# HB-UNI-SenAct-8-8-RC_V1_1.net
KiCad netlist of a schematic drawn in EAGLE
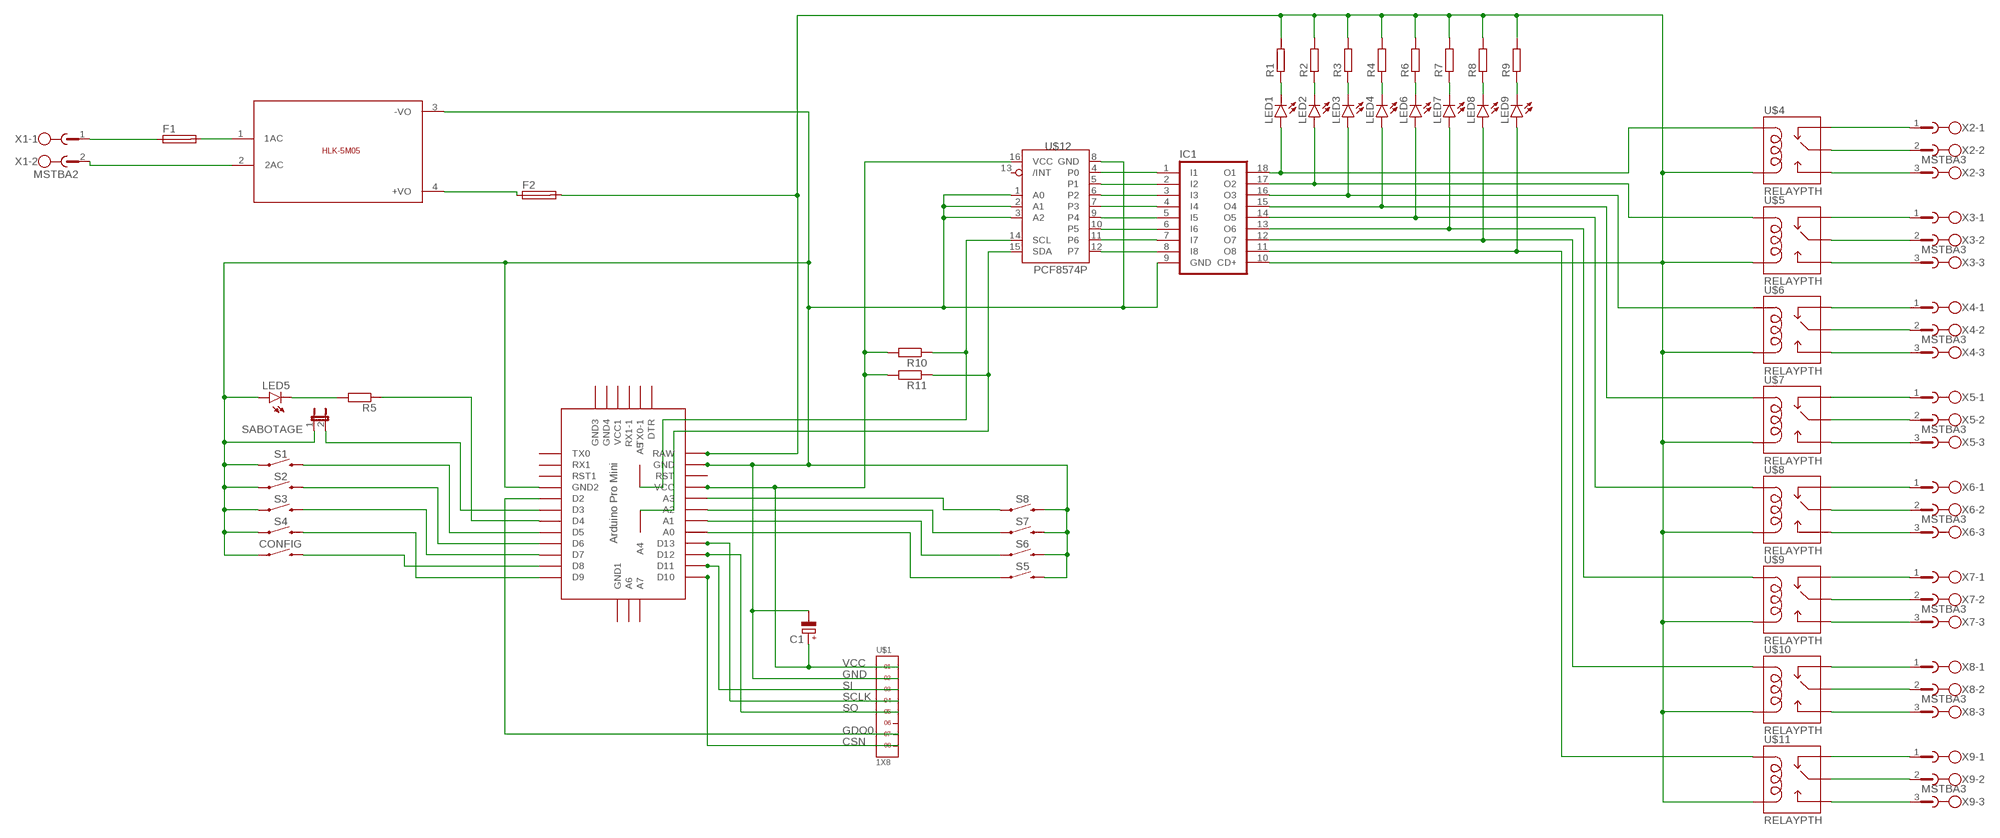
[diagram p0: schematic, sheet 1]

(export (version "E")
  (design (tool "Eeschema 10.0.6"))
  (components
    (comp (ref "C1")
      (value "CPOL-EUE2.5-5")
      (footprint "eagle-import:E2,5-5")
      (libsource (lib "eagle-import") (part "CPOL-EUE2.5-5"))
    )
    (comp (ref "CONFIG")
      (value "MOMENTARY-SWITCH-SPST-PTH-6.0MM-KIT")
      (footprint "eagle-import:TACTILE_SWITCH_PTH_6.0MM_KIT")
      (libsource (lib "eagle-import") (part "MOMENTARY-SWITCH-SPST-PTH-6.0MM-KIT"))
    )
    (comp (ref "F1")
      (value "SH22,5A")
      (footprint "eagle-import:SH22,5A")
      (fields (field (name "MPN") "0031.7701.11"))
      (libsource (lib "eagle-import") (part "SH22,5A"))
    )
    (comp (ref "F2")
      (value "SH22,5A")
      (footprint "eagle-import:SH22,5A")
      (fields (field (name "MPN") "0031.7701.11"))
      (libsource (lib "eagle-import") (part "SH22,5A"))
    )
    (comp (ref "IC1")
      (value "ULN2803A")
      (footprint "eagle-import:DIL18")
      (libsource (lib "eagle-import") (part "ULN2803A"))
    )
    (comp (ref "LED1")
      (value "LED3MM")
      (footprint "eagle-import:LED3MM")
      (libsource (lib "eagle-import") (part "LED3MM"))
    )
    (comp (ref "LED2")
      (value "LED3MM")
      (footprint "eagle-import:LED3MM")
      (libsource (lib "eagle-import") (part "LED3MM"))
    )
    (comp (ref "LED3")
      (value "LED3MM")
      (footprint "eagle-import:LED3MM")
      (libsource (lib "eagle-import") (part "LED3MM"))
    )
    (comp (ref "LED4")
      (value "LED3MM")
      (footprint "eagle-import:LED3MM")
      (libsource (lib "eagle-import") (part "LED3MM"))
    )
    (comp (ref "LED5")
      (value "LED3MM")
      (footprint "eagle-import:LED3MM")
      (libsource (lib "eagle-import") (part "LED3MM"))
    )
    (comp (ref "LED6")
      (value "LED3MM")
      (footprint "eagle-import:LED3MM")
      (libsource (lib "eagle-import") (part "LED3MM"))
    )
    (comp (ref "LED7")
      (value "LED3MM")
      (footprint "eagle-import:LED3MM")
      (libsource (lib "eagle-import") (part "LED3MM"))
    )
    (comp (ref "LED8")
      (value "LED3MM")
      (footprint "eagle-import:LED3MM")
      (libsource (lib "eagle-import") (part "LED3MM"))
    )
    (comp (ref "LED9")
      (value "LED3MM")
      (footprint "eagle-import:LED3MM")
      (libsource (lib "eagle-import") (part "LED3MM"))
    )
    (comp (ref "R1")
      (value "R-EU_0309/10")
      (footprint "eagle-import:0309_10")
      (libsource (lib "eagle-import") (part "R-EU_0309/10"))
    )
    (comp (ref "R2")
      (value "R-EU_0309/10")
      (footprint "eagle-import:0309_10")
      (libsource (lib "eagle-import") (part "R-EU_0309/10"))
    )
    (comp (ref "R3")
      (value "R-EU_0309/10")
      (footprint "eagle-import:0309_10")
      (libsource (lib "eagle-import") (part "R-EU_0309/10"))
    )
    (comp (ref "R4")
      (value "R-EU_0309/10")
      (footprint "eagle-import:0309_10")
      (libsource (lib "eagle-import") (part "R-EU_0309/10"))
    )
    (comp (ref "R5")
      (value "R-EU_0309/10")
      (footprint "eagle-import:0309_10")
      (libsource (lib "eagle-import") (part "R-EU_0309/10"))
    )
    (comp (ref "R6")
      (value "R-EU_0309/10")
      (footprint "eagle-import:0309_10")
      (libsource (lib "eagle-import") (part "R-EU_0309/10"))
    )
    (comp (ref "R7")
      (value "R-EU_0309/10")
      (footprint "eagle-import:0309_10")
      (libsource (lib "eagle-import") (part "R-EU_0309/10"))
    )
    (comp (ref "R8")
      (value "R-EU_0309/10")
      (footprint "eagle-import:0309_10")
      (libsource (lib "eagle-import") (part "R-EU_0309/10"))
    )
    (comp (ref "R9")
      (value "R-EU_0309/10")
      (footprint "eagle-import:0309_10")
      (libsource (lib "eagle-import") (part "R-EU_0309/10"))
    )
    (comp (ref "R10")
      (value "R-EU_0309/10")
      (footprint "eagle-import:0309_10")
      (libsource (lib "eagle-import") (part "R-EU_0309/10"))
    )
    (comp (ref "R11")
      (value "R-EU_0309/10")
      (footprint "eagle-import:0309_10")
      (libsource (lib "eagle-import") (part "R-EU_0309/10"))
    )
    (comp (ref "S1")
      (value "MOMENTARY-SWITCH-SPST-PTH-6.0MM")
      (footprint "eagle-import:TACTILE_SWITCH_PTH_6.0MM")
      (libsource (lib "eagle-import") (part "MOMENTARY-SWITCH-SPST-PTH-6.0MM"))
    )
    (comp (ref "S2")
      (value "MOMENTARY-SWITCH-SPST-PTH-6.0MM-KIT")
      (footprint "eagle-import:TACTILE_SWITCH_PTH_6.0MM_KIT")
      (libsource (lib "eagle-import") (part "MOMENTARY-SWITCH-SPST-PTH-6.0MM-KIT"))
    )
    (comp (ref "S3")
      (value "MOMENTARY-SWITCH-SPST-PTH-6.0MM-KIT")
      (footprint "eagle-import:TACTILE_SWITCH_PTH_6.0MM_KIT")
      (libsource (lib "eagle-import") (part "MOMENTARY-SWITCH-SPST-PTH-6.0MM-KIT"))
    )
    (comp (ref "S4")
      (value "MOMENTARY-SWITCH-SPST-PTH-6.0MM-KIT")
      (footprint "eagle-import:TACTILE_SWITCH_PTH_6.0MM_KIT")
      (libsource (lib "eagle-import") (part "MOMENTARY-SWITCH-SPST-PTH-6.0MM-KIT"))
    )
    (comp (ref "S5")
      (value "MOMENTARY-SWITCH-SPST-PTH-6.0MM-KIT")
      (footprint "eagle-import:TACTILE_SWITCH_PTH_6.0MM_KIT")
      (libsource (lib "eagle-import") (part "MOMENTARY-SWITCH-SPST-PTH-6.0MM-KIT"))
    )
    (comp (ref "S6")
      (value "MOMENTARY-SWITCH-SPST-PTH-6.0MM-KIT")
      (footprint "eagle-import:TACTILE_SWITCH_PTH_6.0MM_KIT")
      (libsource (lib "eagle-import") (part "MOMENTARY-SWITCH-SPST-PTH-6.0MM-KIT"))
    )
    (comp (ref "S7")
      (value "MOMENTARY-SWITCH-SPST-PTH-6.0MM-KIT")
      (footprint "eagle-import:TACTILE_SWITCH_PTH_6.0MM_KIT")
      (libsource (lib "eagle-import") (part "MOMENTARY-SWITCH-SPST-PTH-6.0MM-KIT"))
    )
    (comp (ref "S8")
      (value "MOMENTARY-SWITCH-SPST-PTH-6.0MM-KIT")
      (footprint "eagle-import:TACTILE_SWITCH_PTH_6.0MM_KIT")
      (libsource (lib "eagle-import") (part "MOMENTARY-SWITCH-SPST-PTH-6.0MM-KIT"))
    )
    (comp (ref "SABOTAGE")
      (value "JP1E")
      (footprint "eagle-import:JP1")
      (libsource (lib "eagle-import") (part "JP1E"))
    )
    (comp (ref "U$1")
      (value "1X8")
      (footprint "eagle-import:1X8")
      (libsource (lib "eagle-import") (part "1X8"))
    )
    (comp (ref "U$2")
      (value "ABK-PRO-MINI")
      (footprint "eagle-import:ABK-PRO-MINI")
      (libsource (lib "eagle-import") (part "ABK-PRO-MINI"))
    )
    (comp (ref "U$3")
      (value "5VDC/5W")
      (footprint "eagle-import:HLK-5M05")
      (libsource (lib "eagle-import") (part "HLK-5M05"))
    )
    (comp (ref "U$4")
      (value "RELAYPTH")
      (footprint "eagle-import:SRD-05VDC-SL-C")
      (libsource (lib "eagle-import") (part "RELAYPTH"))
    )
    (comp (ref "U$5")
      (value "RELAYPTH")
      (footprint "eagle-import:SRD-05VDC-SL-C")
      (libsource (lib "eagle-import") (part "RELAYPTH"))
    )
    (comp (ref "U$6")
      (value "RELAYPTH")
      (footprint "eagle-import:SRD-05VDC-SL-C")
      (libsource (lib "eagle-import") (part "RELAYPTH"))
    )
    (comp (ref "U$7")
      (value "RELAYPTH")
      (footprint "eagle-import:SRD-05VDC-SL-C")
      (libsource (lib "eagle-import") (part "RELAYPTH"))
    )
    (comp (ref "U$8")
      (value "RELAYPTH")
      (footprint "eagle-import:SRD-05VDC-SL-C")
      (libsource (lib "eagle-import") (part "RELAYPTH"))
    )
    (comp (ref "U$9")
      (value "RELAYPTH")
      (footprint "eagle-import:SRD-05VDC-SL-C")
      (libsource (lib "eagle-import") (part "RELAYPTH"))
    )
    (comp (ref "U$10")
      (value "RELAYPTH")
      (footprint "eagle-import:SRD-05VDC-SL-C")
      (libsource (lib "eagle-import") (part "RELAYPTH"))
    )
    (comp (ref "U$11")
      (value "RELAYPTH")
      (footprint "eagle-import:SRD-05VDC-SL-C")
      (libsource (lib "eagle-import") (part "RELAYPTH"))
    )
    (comp (ref "U$12")
      (value "PCF8574P")
      (footprint "eagle-import:DIL16")
      (libsource (lib "eagle-import") (part "PCF8574P"))
    )
    (comp (ref "X1")
      (value "MSTBA2")
      (footprint "eagle-import:MSTBA2")
      (fields (field (name "MF") "FARNELL") (field (name "MPN") "1757242"))
      (libsource (lib "eagle-import") (part "MSTBA2"))
    )
    (comp (ref "X2")
      (value "MSTBA3")
      (footprint "eagle-import:MSTBA3")
      (fields (field (name "MF") "FARNELL") (field (name "MPN") "1757255"))
      (libsource (lib "eagle-import") (part "MSTBA3"))
    )
    (comp (ref "X3")
      (value "MSTBA3")
      (footprint "eagle-import:MSTBA3")
      (fields (field (name "MF") "FARNELL") (field (name "MPN") "1757255"))
      (libsource (lib "eagle-import") (part "MSTBA3"))
    )
    (comp (ref "X4")
      (value "MSTBA3")
      (footprint "eagle-import:MSTBA3")
      (fields (field (name "MF") "FARNELL") (field (name "MPN") "1757255"))
      (libsource (lib "eagle-import") (part "MSTBA3"))
    )
    (comp (ref "X5")
      (value "MSTBA3")
      (footprint "eagle-import:MSTBA3")
      (fields (field (name "MF") "FARNELL") (field (name "MPN") "1757255"))
      (libsource (lib "eagle-import") (part "MSTBA3"))
    )
    (comp (ref "X6")
      (value "MSTBA3")
      (footprint "eagle-import:MSTBA3")
      (fields (field (name "MF") "FARNELL") (field (name "MPN") "1757255"))
      (libsource (lib "eagle-import") (part "MSTBA3"))
    )
    (comp (ref "X7")
      (value "MSTBA3")
      (footprint "eagle-import:MSTBA3")
      (fields (field (name "MF") "FARNELL") (field (name "MPN") "1757255"))
      (libsource (lib "eagle-import") (part "MSTBA3"))
    )
    (comp (ref "X8")
      (value "MSTBA3")
      (footprint "eagle-import:MSTBA3")
      (fields (field (name "MF") "FARNELL") (field (name "MPN") "1757255"))
      (libsource (lib "eagle-import") (part "MSTBA3"))
    )
    (comp (ref "X9")
      (value "MSTBA3")
      (footprint "eagle-import:MSTBA3")
      (fields (field (name "MF") "FARNELL") (field (name "MPN") "1757255"))
      (libsource (lib "eagle-import") (part "MSTBA3"))
    )
  )
  (nets
    (net (code "1") (name "/CSN") (class "Default")
      (node (ref "U$1") (pin "8") (pinfunction "8_8") (pintype "bidirectional"))
      (node (ref "U$2") (pin "D10") (pinfunction "D10_D10") (pintype "bidirectional"))
    )
    (net (code "2") (name "/GDO0") (class "Default")
      (node (ref "U$1") (pin "7") (pinfunction "7_7") (pintype "bidirectional"))
      (node (ref "U$2") (pin "D2") (pinfunction "D2_D2") (pintype "bidirectional"))
    )
    (net (code "3") (name "/GND") (class "Default")
      (node (ref "C1") (pin "-") (pinfunction "-_-") (pintype "passive"))
      (node (ref "CONFIG") (pin "1") (pinfunction "1_1") (pintype "passive"))
      (node (ref "IC1") (pin "9") (pinfunction "GND_9") (pintype "power_in"))
      (node (ref "LED5") (pin "A") (pinfunction "A_A") (pintype "passive"))
      (node (ref "S1") (pin "1") (pinfunction "1_1") (pintype "passive"))
      (node (ref "S2") (pin "1") (pinfunction "1_1") (pintype "passive"))
      (node (ref "S3") (pin "1") (pinfunction "1_1") (pintype "passive"))
      (node (ref "S4") (pin "1") (pinfunction "1_1") (pintype "passive"))
      (node (ref "S5") (pin "3") (pinfunction "2_3") (pintype "passive"))
      (node (ref "S6") (pin "3") (pinfunction "2_3") (pintype "passive"))
      (node (ref "S7") (pin "3") (pinfunction "2_3") (pintype "passive"))
      (node (ref "S8") (pin "3") (pinfunction "2_3") (pintype "passive"))
      (node (ref "SABOTAGE") (pin "1") (pinfunction "1_1") (pintype "passive"))
      (node (ref "U$1") (pin "2") (pinfunction "2_2") (pintype "bidirectional"))
      (node (ref "U$12") (pin "1") (pinfunction "A0_1") (pintype "input"))
      (node (ref "U$12") (pin "2") (pinfunction "A1_2") (pintype "input"))
      (node (ref "U$12") (pin "3") (pinfunction "A2_3") (pintype "input"))
      (node (ref "U$12") (pin "8") (pinfunction "GND_8") (pintype "power_in"))
      (node (ref "U$2") (pin "GND") (pinfunction "GND_GND") (pintype "bidirectional"))
      (node (ref "U$2") (pin "GND1") (pinfunction "GND2_GND1") (pintype "bidirectional"))
      (node (ref "U$3") (pin "3") (pinfunction "-VO_3") (pintype "bidirectional"))
    )
    (net (code "4") (name "/SCLK") (class "Default")
      (node (ref "U$1") (pin "4") (pinfunction "4_4") (pintype "bidirectional"))
      (node (ref "U$2") (pin "D13") (pinfunction "D13_D13") (pintype "bidirectional"))
    )
    (net (code "5") (name "/SI") (class "Default")
      (node (ref "U$1") (pin "3") (pinfunction "3_3") (pintype "bidirectional"))
      (node (ref "U$2") (pin "D11") (pinfunction "D11_D11") (pintype "bidirectional"))
    )
    (net (code "6") (name "/SO") (class "Default")
      (node (ref "U$1") (pin "5") (pinfunction "5_5") (pintype "bidirectional"))
      (node (ref "U$2") (pin "D12") (pinfunction "D12_D12") (pintype "bidirectional"))
    )
    (net (code "7") (name "/VCC") (class "Default")
      (node (ref "C1") (pin "+") (pinfunction "+_+") (pintype "passive"))
      (node (ref "R10") (pin "2") (pinfunction "2_2") (pintype "passive"))
      (node (ref "R11") (pin "2") (pinfunction "2_2") (pintype "passive"))
      (node (ref "U$1") (pin "1") (pinfunction "1_1") (pintype "bidirectional"))
      (node (ref "U$12") (pin "16") (pinfunction "VCC_16") (pintype "power_in"))
      (node (ref "U$2") (pin "VCC") (pinfunction "VCC_VCC") (pintype "bidirectional"))
    )
    (net (code "8") (name "Net-(CONFIG-2)") (class "Default")
      (node (ref "CONFIG") (pin "3") (pinfunction "2_3") (pintype "passive"))
      (node (ref "U$2") (pin "D8") (pinfunction "D8_D8") (pintype "bidirectional"))
    )
    (net (code "9") (name "Net-(F1-Pad1)") (class "Default")
      (node (ref "F1") (pin "1") (pinfunction "1_1") (pintype "passive"))
      (node (ref "X1") (pin "1") (pinfunction "1_1") (pintype "passive"))
    )
    (net (code "10") (name "Net-(IC1-CD+)") (class "Default")
      (node (ref "F2") (pin "2") (pinfunction "2_2") (pintype "passive"))
      (node (ref "IC1") (pin "10") (pinfunction "CD+_10") (pintype "passive"))
      (node (ref "R1") (pin "2") (pinfunction "2_2") (pintype "passive"))
      (node (ref "R2") (pin "2") (pinfunction "2_2") (pintype "passive"))
      (node (ref "R3") (pin "2") (pinfunction "2_2") (pintype "passive"))
      (node (ref "R4") (pin "2") (pinfunction "2_2") (pintype "passive"))
      (node (ref "R6") (pin "2") (pinfunction "2_2") (pintype "passive"))
      (node (ref "R7") (pin "2") (pinfunction "2_2") (pintype "passive"))
      (node (ref "R8") (pin "2") (pinfunction "2_2") (pintype "passive"))
      (node (ref "R9") (pin "2") (pinfunction "2_2") (pintype "passive"))
      (node (ref "U$10") (pin "COIL0") (pinfunction "COIL0_COIL0") (pintype "bidirectional"))
      (node (ref "U$11") (pin "COIL0") (pinfunction "COIL0_COIL0") (pintype "bidirectional"))
      (node (ref "U$2") (pin "RAW") (pinfunction "RAW_RAW") (pintype "bidirectional"))
      (node (ref "U$4") (pin "COIL0") (pinfunction "COIL0_COIL0") (pintype "bidirectional"))
      (node (ref "U$5") (pin "COIL0") (pinfunction "COIL0_COIL0") (pintype "bidirectional"))
      (node (ref "U$6") (pin "COIL0") (pinfunction "COIL0_COIL0") (pintype "bidirectional"))
      (node (ref "U$7") (pin "COIL0") (pinfunction "COIL0_COIL0") (pintype "bidirectional"))
      (node (ref "U$8") (pin "COIL0") (pinfunction "COIL0_COIL0") (pintype "bidirectional"))
      (node (ref "U$9") (pin "COIL0") (pinfunction "COIL0_COIL0") (pintype "bidirectional"))
    )
    (net (code "11") (name "Net-(IC1-I1)") (class "Default")
      (node (ref "IC1") (pin "1") (pinfunction "I1_1") (pintype "input"))
      (node (ref "U$12") (pin "4") (pinfunction "P0_4") (pintype "bidirectional"))
    )
    (net (code "12") (name "Net-(IC1-I2)") (class "Default")
      (node (ref "IC1") (pin "2") (pinfunction "I2_2") (pintype "input"))
      (node (ref "U$12") (pin "5") (pinfunction "P1_5") (pintype "bidirectional"))
    )
    (net (code "13") (name "Net-(IC1-I3)") (class "Default")
      (node (ref "IC1") (pin "3") (pinfunction "I3_3") (pintype "input"))
      (node (ref "U$12") (pin "6") (pinfunction "P2_6") (pintype "bidirectional"))
    )
    (net (code "14") (name "Net-(IC1-I4)") (class "Default")
      (node (ref "IC1") (pin "4") (pinfunction "I4_4") (pintype "input"))
      (node (ref "U$12") (pin "7") (pinfunction "P3_7") (pintype "bidirectional"))
    )
    (net (code "15") (name "Net-(IC1-I5)") (class "Default")
      (node (ref "IC1") (pin "5") (pinfunction "I5_5") (pintype "input"))
      (node (ref "U$12") (pin "9") (pinfunction "P4_9") (pintype "bidirectional"))
    )
    (net (code "16") (name "Net-(IC1-I6)") (class "Default")
      (node (ref "IC1") (pin "6") (pinfunction "I6_6") (pintype "input"))
      (node (ref "U$12") (pin "10") (pinfunction "P5_10") (pintype "bidirectional"))
    )
    (net (code "17") (name "Net-(IC1-I7)") (class "Default")
      (node (ref "IC1") (pin "7") (pinfunction "I7_7") (pintype "input"))
      (node (ref "U$12") (pin "11") (pinfunction "P6_11") (pintype "bidirectional"))
    )
    (net (code "18") (name "Net-(IC1-I8)") (class "Default")
      (node (ref "IC1") (pin "8") (pinfunction "I8_8") (pintype "input"))
      (node (ref "U$12") (pin "12") (pinfunction "P7_12") (pintype "bidirectional"))
    )
    (net (code "19") (name "Net-(IC1-O1)") (class "Default")
      (node (ref "IC1") (pin "18") (pinfunction "O1_18") (pintype "open_collector"))
      (node (ref "LED1") (pin "A") (pinfunction "A_A") (pintype "passive"))
      (node (ref "U$4") (pin "COIL1") (pinfunction "COIL1_COIL1") (pintype "bidirectional"))
    )
    (net (code "20") (name "Net-(IC1-O2)") (class "Default")
      (node (ref "IC1") (pin "17") (pinfunction "O2_17") (pintype "open_collector"))
      (node (ref "LED2") (pin "A") (pinfunction "A_A") (pintype "passive"))
      (node (ref "U$5") (pin "COIL1") (pinfunction "COIL1_COIL1") (pintype "bidirectional"))
    )
    (net (code "21") (name "Net-(IC1-O3)") (class "Default")
      (node (ref "IC1") (pin "16") (pinfunction "O3_16") (pintype "open_collector"))
      (node (ref "LED3") (pin "A") (pinfunction "A_A") (pintype "passive"))
      (node (ref "U$6") (pin "COIL1") (pinfunction "COIL1_COIL1") (pintype "bidirectional"))
    )
    (net (code "22") (name "Net-(IC1-O4)") (class "Default")
      (node (ref "IC1") (pin "15") (pinfunction "O4_15") (pintype "open_collector"))
      (node (ref "LED4") (pin "A") (pinfunction "A_A") (pintype "passive"))
      (node (ref "U$7") (pin "COIL1") (pinfunction "COIL1_COIL1") (pintype "bidirectional"))
    )
    (net (code "23") (name "Net-(IC1-O5)") (class "Default")
      (node (ref "IC1") (pin "14") (pinfunction "O5_14") (pintype "open_collector"))
      (node (ref "LED6") (pin "A") (pinfunction "A_A") (pintype "passive"))
      (node (ref "U$8") (pin "COIL1") (pinfunction "COIL1_COIL1") (pintype "bidirectional"))
    )
    (net (code "24") (name "Net-(IC1-O6)") (class "Default")
      (node (ref "IC1") (pin "13") (pinfunction "O6_13") (pintype "open_collector"))
      (node (ref "LED7") (pin "A") (pinfunction "A_A") (pintype "passive"))
      (node (ref "U$9") (pin "COIL1") (pinfunction "COIL1_COIL1") (pintype "bidirectional"))
    )
    (net (code "25") (name "Net-(IC1-O7)") (class "Default")
      (node (ref "IC1") (pin "12") (pinfunction "O7_12") (pintype "open_collector"))
      (node (ref "LED8") (pin "A") (pinfunction "A_A") (pintype "passive"))
      (node (ref "U$10") (pin "COIL1") (pinfunction "COIL1_COIL1") (pintype "bidirectional"))
    )
    (net (code "26") (name "Net-(IC1-O8)") (class "Default")
      (node (ref "IC1") (pin "11") (pinfunction "O8_11") (pintype "open_collector"))
      (node (ref "LED9") (pin "A") (pinfunction "A_A") (pintype "passive"))
      (node (ref "U$11") (pin "COIL1") (pinfunction "COIL1_COIL1") (pintype "bidirectional"))
    )
    (net (code "27") (name "Net-(LED1-C)") (class "Default")
      (node (ref "LED1") (pin "K") (pinfunction "C_K") (pintype "passive"))
      (node (ref "R1") (pin "1") (pinfunction "1_1") (pintype "passive"))
    )
    (net (code "28") (name "Net-(LED2-C)") (class "Default")
      (node (ref "LED2") (pin "K") (pinfunction "C_K") (pintype "passive"))
      (node (ref "R2") (pin "1") (pinfunction "1_1") (pintype "passive"))
    )
    (net (code "29") (name "Net-(LED3-C)") (class "Default")
      (node (ref "LED3") (pin "K") (pinfunction "C_K") (pintype "passive"))
      (node (ref "R3") (pin "1") (pinfunction "1_1") (pintype "passive"))
    )
    (net (code "30") (name "Net-(LED4-C)") (class "Default")
      (node (ref "LED4") (pin "K") (pinfunction "C_K") (pintype "passive"))
      (node (ref "R4") (pin "1") (pinfunction "1_1") (pintype "passive"))
    )
    (net (code "31") (name "Net-(LED5-C)") (class "Default")
      (node (ref "LED5") (pin "K") (pinfunction "C_K") (pintype "passive"))
      (node (ref "R5") (pin "2") (pinfunction "2_2") (pintype "passive"))
    )
    (net (code "32") (name "Net-(LED6-C)") (class "Default")
      (node (ref "LED6") (pin "K") (pinfunction "C_K") (pintype "passive"))
      (node (ref "R6") (pin "1") (pinfunction "1_1") (pintype "passive"))
    )
    (net (code "33") (name "Net-(LED7-C)") (class "Default")
      (node (ref "LED7") (pin "K") (pinfunction "C_K") (pintype "passive"))
      (node (ref "R7") (pin "1") (pinfunction "1_1") (pintype "passive"))
    )
    (net (code "34") (name "Net-(LED8-C)") (class "Default")
      (node (ref "LED8") (pin "K") (pinfunction "C_K") (pintype "passive"))
      (node (ref "R8") (pin "1") (pinfunction "1_1") (pintype "passive"))
    )
    (net (code "35") (name "Net-(LED9-C)") (class "Default")
      (node (ref "LED9") (pin "K") (pinfunction "C_K") (pintype "passive"))
      (node (ref "R9") (pin "1") (pinfunction "1_1") (pintype "passive"))
    )
    (net (code "36") (name "Net-(R5-Pad1)") (class "Default")
      (node (ref "R5") (pin "1") (pinfunction "1_1") (pintype "passive"))
      (node (ref "U$2") (pin "D4") (pinfunction "D4_D4") (pintype "bidirectional"))
    )
    (net (code "37") (name "Net-(S1-2)") (class "Default")
      (node (ref "S1") (pin "3") (pinfunction "2_3") (pintype "passive"))
      (node (ref "U$2") (pin "D5") (pinfunction "D5_D5") (pintype "bidirectional"))
    )
    (net (code "38") (name "Net-(S2-2)") (class "Default")
      (node (ref "S2") (pin "3") (pinfunction "2_3") (pintype "passive"))
      (node (ref "U$2") (pin "D6") (pinfunction "D6_D6") (pintype "bidirectional"))
    )
    (net (code "39") (name "Net-(S3-2)") (class "Default")
      (node (ref "S3") (pin "3") (pinfunction "2_3") (pintype "passive"))
      (node (ref "U$2") (pin "D7") (pinfunction "D7_D7") (pintype "bidirectional"))
    )
    (net (code "40") (name "Net-(S4-2)") (class "Default")
      (node (ref "S4") (pin "3") (pinfunction "2_3") (pintype "passive"))
      (node (ref "U$2") (pin "D9") (pinfunction "D9_D9") (pintype "bidirectional"))
    )
    (net (code "41") (name "Net-(S5-Pad1)") (class "Default")
      (node (ref "S5") (pin "1") (pinfunction "1_1") (pintype "passive"))
      (node (ref "U$2") (pin "A0") (pinfunction "A0_A0") (pintype "bidirectional"))
    )
    (net (code "42") (name "Net-(S6-Pad1)") (class "Default")
      (node (ref "S6") (pin "1") (pinfunction "1_1") (pintype "passive"))
      (node (ref "U$2") (pin "A1") (pinfunction "A1_A1") (pintype "bidirectional"))
    )
    (net (code "43") (name "Net-(S7-Pad1)") (class "Default")
      (node (ref "S7") (pin "1") (pinfunction "1_1") (pintype "passive"))
      (node (ref "U$2") (pin "A2") (pinfunction "A2_A2") (pintype "bidirectional"))
    )
    (net (code "44") (name "Net-(S8-Pad1)") (class "Default")
      (node (ref "S8") (pin "1") (pinfunction "1_1") (pintype "passive"))
      (node (ref "U$2") (pin "A3") (pinfunction "A3_A3") (pintype "bidirectional"))
    )
    (net (code "45") (name "Net-(SABOTAGE-Pad2)") (class "Default")
      (node (ref "SABOTAGE") (pin "2") (pinfunction "2_2") (pintype "passive"))
      (node (ref "U$2") (pin "D3") (pinfunction "D3_D3") (pintype "bidirectional"))
    )
    (net (code "46") (name "Net-(U$3-+VO)") (class "Default")
      (node (ref "F2") (pin "1") (pinfunction "1_1") (pintype "passive"))
      (node (ref "U$3") (pin "4") (pinfunction "+VO_4") (pintype "bidirectional"))
    )
    (net (code "47") (name "Net-(U$3-1AC)") (class "Default")
      (node (ref "F1") (pin "2") (pinfunction "2_2") (pintype "passive"))
      (node (ref "U$3") (pin "1") (pinfunction "1AC_1") (pintype "bidirectional"))
    )
    (net (code "48") (name "Net-(U$3-2AC)") (class "Default")
      (node (ref "U$3") (pin "2") (pinfunction "2AC_2") (pintype "bidirectional"))
      (node (ref "X1") (pin "2") (pinfunction "1_2") (pintype "passive"))
    )
    (net (code "49") (name "Net-(U$4-SWCLOSE)") (class "Default")
      (node (ref "U$4") (pin "SWCLOSED") (pinfunction "SWCLOSE_SWCLOSED") (pintype "bidirectional"))
      (node (ref "X2") (pin "1") (pinfunction "1_1") (pintype "passive"))
    )
    (net (code "50") (name "Net-(U$5-SWCLOSE)") (class "Default")
      (node (ref "U$5") (pin "SWCLOSED") (pinfunction "SWCLOSE_SWCLOSED") (pintype "bidirectional"))
      (node (ref "X3") (pin "1") (pinfunction "1_1") (pintype "passive"))
    )
    (net (code "51") (name "Net-(U$6-SWCLOSE)") (class "Default")
      (node (ref "U$6") (pin "SWCLOSED") (pinfunction "SWCLOSE_SWCLOSED") (pintype "bidirectional"))
      (node (ref "X4") (pin "1") (pinfunction "1_1") (pintype "passive"))
    )
    (net (code "52") (name "Net-(U$7-SWCLOSE)") (class "Default")
      (node (ref "U$7") (pin "SWCLOSED") (pinfunction "SWCLOSE_SWCLOSED") (pintype "bidirectional"))
      (node (ref "X5") (pin "1") (pinfunction "1_1") (pintype "passive"))
    )
    (net (code "53") (name "Net-(U$8-SWCLOSE)") (class "Default")
      (node (ref "U$8") (pin "SWCLOSED") (pinfunction "SWCLOSE_SWCLOSED") (pintype "bidirectional"))
      (node (ref "X6") (pin "1") (pinfunction "1_1") (pintype "passive"))
    )
    (net (code "54") (name "Net-(U$9-SWCLOSE)") (class "Default")
      (node (ref "U$9") (pin "SWCLOSED") (pinfunction "SWCLOSE_SWCLOSED") (pintype "bidirectional"))
      (node (ref "X7") (pin "1") (pinfunction "1_1") (pintype "passive"))
    )
    (net (code "55") (name "Net-(U$10-SWCLOSE)") (class "Default")
      (node (ref "U$10") (pin "SWCLOSED") (pinfunction "SWCLOSE_SWCLOSED") (pintype "bidirectional"))
      (node (ref "X8") (pin "1") (pinfunction "1_1") (pintype "passive"))
    )
    (net (code "56") (name "Net-(U$11-SWCLOSE)") (class "Default")
      (node (ref "U$11") (pin "SWCLOSED") (pinfunction "SWCLOSE_SWCLOSED") (pintype "bidirectional"))
      (node (ref "X9") (pin "1") (pinfunction "1_1") (pintype "passive"))
    )
    (net (code "57") (name "Net-(U$12-SCL)") (class "Default")
      (node (ref "R10") (pin "1") (pinfunction "1_1") (pintype "passive"))
      (node (ref "U$12") (pin "14") (pinfunction "SCL_14") (pintype "input"))
      (node (ref "U$2") (pin "A5") (pinfunction "A5_A5") (pintype "bidirectional"))
    )
    (net (code "58") (name "Net-(U$12-SDA)") (class "Default")
      (node (ref "R11") (pin "1") (pinfunction "1_1") (pintype "passive"))
      (node (ref "U$12") (pin "15") (pinfunction "SDA_15") (pintype "bidirectional"))
      (node (ref "U$2") (pin "A4") (pinfunction "A4_A4") (pintype "bidirectional"))
    )
    (net (code "59") (name "Net-(X2B-1)") (class "Default")
      (node (ref "U$4") (pin "SWCOMMON") (pinfunction "SWCOMMON_SWCOMMON") (pintype "bidirectional"))
      (node (ref "X2") (pin "2") (pinfunction "1_2") (pintype "passive"))
    )
    (net (code "60") (name "Net-(X2C-1)") (class "Default")
      (node (ref "U$4") (pin "SWOPEN") (pinfunction "SWOPEN_SWOPEN") (pintype "bidirectional"))
      (node (ref "X2") (pin "3") (pinfunction "1_3") (pintype "passive"))
    )
    (net (code "61") (name "Net-(X3B-1)") (class "Default")
      (node (ref "U$5") (pin "SWCOMMON") (pinfunction "SWCOMMON_SWCOMMON") (pintype "bidirectional"))
      (node (ref "X3") (pin "2") (pinfunction "1_2") (pintype "passive"))
    )
    (net (code "62") (name "Net-(X3C-1)") (class "Default")
      (node (ref "U$5") (pin "SWOPEN") (pinfunction "SWOPEN_SWOPEN") (pintype "bidirectional"))
      (node (ref "X3") (pin "3") (pinfunction "1_3") (pintype "passive"))
    )
    (net (code "63") (name "Net-(X4B-1)") (class "Default")
      (node (ref "U$6") (pin "SWCOMMON") (pinfunction "SWCOMMON_SWCOMMON") (pintype "bidirectional"))
      (node (ref "X4") (pin "2") (pinfunction "1_2") (pintype "passive"))
    )
    (net (code "64") (name "Net-(X4C-1)") (class "Default")
      (node (ref "U$6") (pin "SWOPEN") (pinfunction "SWOPEN_SWOPEN") (pintype "bidirectional"))
      (node (ref "X4") (pin "3") (pinfunction "1_3") (pintype "passive"))
    )
    (net (code "65") (name "Net-(X5B-1)") (class "Default")
      (node (ref "U$7") (pin "SWCOMMON") (pinfunction "SWCOMMON_SWCOMMON") (pintype "bidirectional"))
      (node (ref "X5") (pin "2") (pinfunction "1_2") (pintype "passive"))
    )
    (net (code "66") (name "Net-(X5C-1)") (class "Default")
      (node (ref "U$7") (pin "SWOPEN") (pinfunction "SWOPEN_SWOPEN") (pintype "bidirectional"))
      (node (ref "X5") (pin "3") (pinfunction "1_3") (pintype "passive"))
    )
    (net (code "67") (name "Net-(X6B-1)") (class "Default")
      (node (ref "U$8") (pin "SWCOMMON") (pinfunction "SWCOMMON_SWCOMMON") (pintype "bidirectional"))
      (node (ref "X6") (pin "2") (pinfunction "1_2") (pintype "passive"))
    )
    (net (code "68") (name "Net-(X6C-1)") (class "Default")
      (node (ref "U$8") (pin "SWOPEN") (pinfunction "SWOPEN_SWOPEN") (pintype "bidirectional"))
      (node (ref "X6") (pin "3") (pinfunction "1_3") (pintype "passive"))
    )
    (net (code "69") (name "Net-(X7B-1)") (class "Default")
      (node (ref "U$9") (pin "SWCOMMON") (pinfunction "SWCOMMON_SWCOMMON") (pintype "bidirectional"))
      (node (ref "X7") (pin "2") (pinfunction "1_2") (pintype "passive"))
    )
    (net (code "70") (name "Net-(X7C-1)") (class "Default")
      (node (ref "U$9") (pin "SWOPEN") (pinfunction "SWOPEN_SWOPEN") (pintype "bidirectional"))
      (node (ref "X7") (pin "3") (pinfunction "1_3") (pintype "passive"))
    )
    (net (code "71") (name "Net-(X8B-1)") (class "Default")
      (node (ref "U$10") (pin "SWCOMMON") (pinfunction "SWCOMMON_SWCOMMON") (pintype "bidirectional"))
      (node (ref "X8") (pin "2") (pinfunction "1_2") (pintype "passive"))
    )
    (net (code "72") (name "Net-(X8C-1)") (class "Default")
      (node (ref "U$10") (pin "SWOPEN") (pinfunction "SWOPEN_SWOPEN") (pintype "bidirectional"))
      (node (ref "X8") (pin "3") (pinfunction "1_3") (pintype "passive"))
    )
    (net (code "73") (name "Net-(X9B-1)") (class "Default")
      (node (ref "U$11") (pin "SWCOMMON") (pinfunction "SWCOMMON_SWCOMMON") (pintype "bidirectional"))
      (node (ref "X9") (pin "2") (pinfunction "1_2") (pintype "passive"))
    )
    (net (code "74") (name "Net-(X9C-1)") (class "Default")
      (node (ref "U$11") (pin "SWOPEN") (pinfunction "SWOPEN_SWOPEN") (pintype "bidirectional"))
      (node (ref "X9") (pin "3") (pinfunction "1_3") (pintype "passive"))
    )
    (net (code "75") (name "unconnected-(U$1-Pad6)") (class "Default")
      (node (ref "U$1") (pin "6") (pinfunction "6_6") (pintype "bidirectional"))
    )
    (net (code "76") (name "unconnected-(U$2-GND1-PadGND4)") (class "Default")
      (node (ref "U$2") (pin "GND4") (pinfunction "GND1_GND4") (pintype "bidirectional"))
    )
    (net (code "77") (name "unconnected-(U$2-GND3-PadGND2)") (class "Default")
      (node (ref "U$2") (pin "GND2") (pinfunction "GND3_GND2") (pintype "bidirectional"))
    )
    (net (code "78") (name "unconnected-(U$2-GND4-PadGND3)") (class "Default")
      (node (ref "U$2") (pin "GND3") (pinfunction "GND4_GND3") (pintype "bidirectional"))
    )
    (net (code "79") (name "unconnected-(U$2-PadA6)") (class "Default")
      (node (ref "U$2") (pin "A6") (pinfunction "A6_A6") (pintype "bidirectional"))
    )
    (net (code "80") (name "unconnected-(U$2-PadA7)") (class "Default")
      (node (ref "U$2") (pin "A7") (pinfunction "A7_A7") (pintype "bidirectional"))
    )
    (net (code "81") (name "unconnected-(U$2-PadDTR)") (class "Default")
      (node (ref "U$2") (pin "DTR") (pinfunction "DTR_DTR") (pintype "bidirectional"))
    )
    (net (code "82") (name "unconnected-(U$2-PadRST)") (class "Default")
      (node (ref "U$2") (pin "RST") (pinfunction "RST_RST") (pintype "bidirectional"))
    )
    (net (code "83") (name "unconnected-(U$2-PadRST1)") (class "Default")
      (node (ref "U$2") (pin "RST1") (pinfunction "RST1_RST1") (pintype "bidirectional"))
    )
    (net (code "84") (name "unconnected-(U$2-PadRX1)") (class "Default")
      (node (ref "U$2") (pin "RX1") (pinfunction "RX1_RX1") (pintype "bidirectional"))
    )
    (net (code "85") (name "unconnected-(U$2-PadRX1-1)") (class "Default")
      (node (ref "U$2") (pin "RX1-1") (pinfunction "RX1-1_RX1-1") (pintype "bidirectional"))
    )
    (net (code "86") (name "unconnected-(U$2-PadTX0)") (class "Default")
      (node (ref "U$2") (pin "TX0") (pinfunction "TX0_TX0") (pintype "bidirectional"))
    )
    (net (code "87") (name "unconnected-(U$2-PadTX0-1)") (class "Default")
      (node (ref "U$2") (pin "TX0-1") (pinfunction "TX0-1_TX0-1") (pintype "bidirectional"))
    )
    (net (code "88") (name "unconnected-(U$2-PadVCC1)") (class "Default")
      (node (ref "U$2") (pin "VCC1") (pinfunction "VCC1_VCC1") (pintype "bidirectional"))
    )
    (net (code "89") (name "unconnected-(U$12-{slash}INT-Pad13)") (class "Default")
      (node (ref "U$12") (pin "13") (pinfunction "/INT_13") (pintype "output"))
    )
  )
)
